# External_Trigger_Buffer.net
KiCad netlist of a schematic drawn in Altium Designer
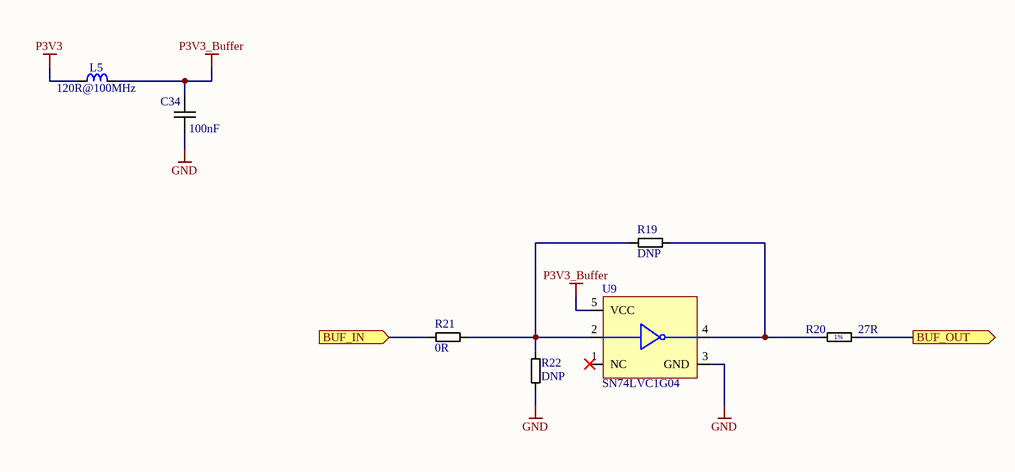
[diagram p0: External_Trigger_Buffer.SchDoc]

(export (version "E")
  (design (tool "Eeschema 10.0.6"))
  (components
    (comp (ref "C34")
      (value "100nF")
      (footprint "CAPC0603X90N")
      (description "Non-polarised capacitor")
      (fields (field (name "MANUFACTURER PART NUMBER") "VJ0603Y104KXJCW1BC"))
      (libsource (lib "Capacitors") (part "Capacitor - non polarized"))
    )
    (comp (ref "L5")
      (value "120R@100MHz")
      (footprint "INDC0603X90N")
      (description "Ferrite Bead")
      (fields (field (name "MANUFACTURER PART NUMBER") "BLM18PG121SN1D") (field (name "TOLERANCE") "25%"))
      (libsource (lib "Inductors") (part "Inductor"))
    )
    (comp (ref "R19")
      (value "DNP")
      (footprint "RESC0603X60N")
      (description "General Purpose Thick Film Chip Resistor")
      (fields (field (name "VOLTAGE") "75V"))
      (libsource (lib "Resistors") (part "Resistor - Generic"))
    )
    (comp (ref "R20")
      (value "27R")
      (footprint "RESC0603X60N")
      (description "General Purpose Thick Film Chip Resistor")
      (fields (field (name "MANUFACTURER PART NUMBER") "WF06P270JTL") (field (name "TOLERANCE") "1%"))
      (libsource (lib "Resistors") (part "Resistor - 1%"))
    )
    (comp (ref "R21")
      (value "0R")
      (footprint "RESC0603X60N")
      (description "General Purpose Thick Film Chip Resistor")
      (fields (field (name "MANUFACTURER PART NUMBER") "AC0603JR-070RL") (field (name "TOLERANCE") "20mOhm"))
      (libsource (lib "Resistors") (part "Resistor - Generic"))
    )
    (comp (ref "R22")
      (value "DNP")
      (footprint "RESC0603X60N")
      (description "General Purpose Thick Film Chip Resistor")
      (fields (field (name "VOLTAGE") "75V"))
      (libsource (lib "Resistors") (part "Resistor - Generic"))
    )
    (comp (ref "U9")
      (value "SN74LVC1G04")
      (description "SINGLE INVERTER GATE")
      (fields (field (name "MANUFACTURER 1 PART NUMBER") "SN74LVC1G04MDBVREP"))
      (libsource (lib "ICs_and_Semiconductors") (part "SN74LVC1G04"))
    )
  )
  (nets
    (net (code "1") (name "/BUF_IN") (class "Default")
      (node (ref "R21") (pin "1") (pinfunction "1_1") (pintype "passive"))
    )
    (net (code "2") (name "/BUF_OUT") (class "Default")
      (node (ref "R20") (pin "2") (pinfunction "2_2") (pintype "passive"))
    )
    (net (code "3") (name "GND") (class "Default")
      (node (ref "C34") (pin "2") (pinfunction "2_2") (pintype "passive"))
      (node (ref "R22") (pin "1") (pinfunction "1_1") (pintype "passive"))
      (node (ref "U9") (pin "3") (pinfunction "GND_3") (pintype "passive"))
    )
    (net (code "4") (name "Net-(U9-A)") (class "Default")
      (node (ref "R19") (pin "1") (pinfunction "1_1") (pintype "passive"))
      (node (ref "R21") (pin "2") (pinfunction "2_2") (pintype "passive"))
      (node (ref "R22") (pin "2") (pinfunction "2_2") (pintype "passive"))
      (node (ref "U9") (pin "2") (pinfunction "A_2") (pintype "passive"))
    )
    (net (code "5") (name "Net-(U9-Y)") (class "Default")
      (node (ref "R19") (pin "2") (pinfunction "2_2") (pintype "passive"))
      (node (ref "R20") (pin "1") (pinfunction "1_1") (pintype "passive"))
      (node (ref "U9") (pin "4") (pinfunction "Y_4") (pintype "passive"))
    )
    (net (code "6") (name "P3V3") (class "Default")
      (node (ref "L5") (pin "1") (pinfunction "1_1") (pintype "passive"))
    )
    (net (code "7") (name "P3V3_Buffer") (class "Default")
      (node (ref "C34") (pin "1") (pinfunction "1_1") (pintype "passive"))
      (node (ref "L5") (pin "2") (pinfunction "2_2") (pintype "passive"))
      (node (ref "U9") (pin "5") (pinfunction "VCC_5") (pintype "passive"))
    )
    (net (code "8") (name "unconnected-(U9-NC-Pad1)") (class "Default")
      (node (ref "U9") (pin "1") (pinfunction "NC_1") (pintype "passive+no_connect"))
    )
  )
)
